# led-drv-noemi.net
KiCad netlist of a schematic drawn in EAGLE
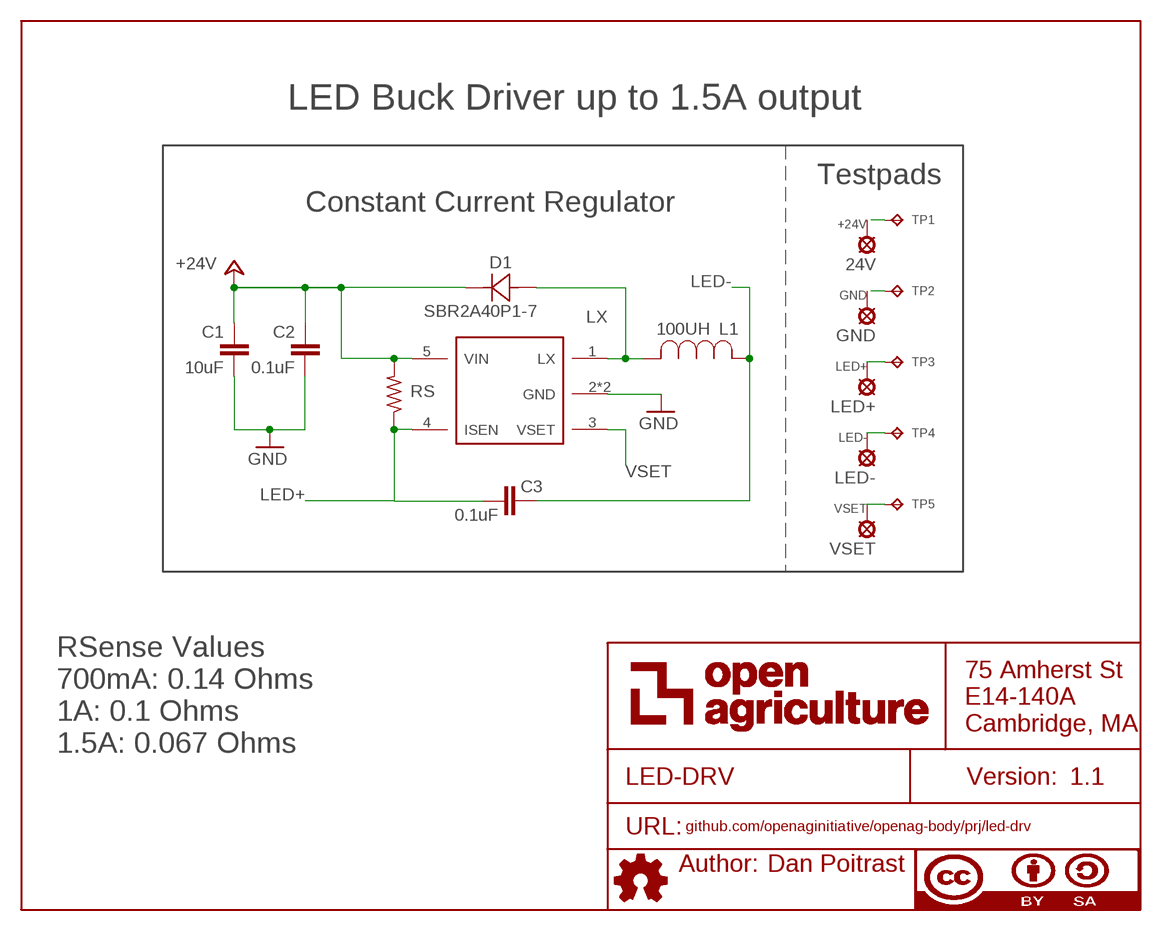
[diagram p0: schematic, sheet 1]

(export (version "E")
  (design (tool "Eeschema 10.0.6"))
  (components
    (comp (ref "24V")
      (value "SE14")
      (footprint "eagle-import:SE14")
      (libsource (lib "eagle-import") (part "SE14"))
    )
    (comp (ref "C1")
      (value "10uF")
      (footprint "eagle-import:C0805")
      (fields (field (name "MANUFACTURER") "Taiyo Yuden") (field (name "MPN") "GMK212BBJ106KG-T"))
      (libsource (lib "eagle-import") (part "10UF-GMK212BBJ106KG-T"))
    )
    (comp (ref "C2")
      (value "0.1uF")
      (footprint "eagle-import:C0603")
      (fields (field (name "MANUFACTURER") "Kemet") (field (name "MPN") "C0603C104K5RACTU"))
      (libsource (lib "eagle-import") (part "0.1UF-C0603C104K5RACTU"))
    )
    (comp (ref "C3")
      (value "0.1uF")
      (footprint "eagle-import:C0603")
      (fields (field (name "MANUFACTURER") "Kemet") (field (name "MPN") "C0603C104K5RACTU"))
      (libsource (lib "eagle-import") (part "0.1UF-C0603C104K5RACTU"))
    )
    (comp (ref "D1")
      (value "SBR2A40P1-7")
      (footprint "eagle-import:POWERDI123")
      (fields (field (name "MANUFACTURER") "Diodes Incorporated"))
      (libsource (lib "eagle-import") (part "SBR2A40P1-7"))
    )
    (comp (ref "GND")
      (value "SE14")
      (footprint "eagle-import:SE14")
      (libsource (lib "eagle-import") (part "SE14"))
    )
    (comp (ref "L1")
      (value "100UH")
      (footprint "eagle-import:IND_BOURNS_SDR1307")
      (libsource (lib "eagle-import") (part "100UH_BOURNES"))
    )
    (comp (ref "LED+")
      (value "SE14")
      (footprint "eagle-import:SE14")
      (libsource (lib "eagle-import") (part "SE14"))
    )
    (comp (ref "LED-")
      (value "SE14")
      (footprint "eagle-import:SE14")
      (libsource (lib "eagle-import") (part "SE14"))
    )
    (comp (ref "RS")
      (value ".06 ohms")
      (footprint "eagle-import:R0805")
      (libsource (lib "eagle-import") (part "6.3OHM-RC0805FR-076R34L"))
    )
    (comp (ref "TP1")
      (value "TPTP06R")
      (footprint "eagle-import:TP06R")
      (libsource (lib "eagle-import") (part "TPTP06R"))
    )
    (comp (ref "TP2")
      (value "TPTP06R")
      (footprint "eagle-import:TP06R")
      (libsource (lib "eagle-import") (part "TPTP06R"))
    )
    (comp (ref "TP3")
      (value "TPTP06R")
      (footprint "eagle-import:TP06R")
      (libsource (lib "eagle-import") (part "TPTP06R"))
    )
    (comp (ref "TP4")
      (value "TPTP06R")
      (footprint "eagle-import:TP06R")
      (libsource (lib "eagle-import") (part "TPTP06R"))
    )
    (comp (ref "TP5")
      (value "TPTP06R")
      (footprint "eagle-import:TP06R")
      (libsource (lib "eagle-import") (part "TPTP06R"))
    )
    (comp (ref "U$6")
      (value "AUTHOR")
      (footprint "eagle-import:AUTHOR")
      (fields (field (name "AUTHOR") "Dan Poitrast"))
      (libsource (lib "eagle-import") (part "AUTHOR"))
    )
    (comp (ref "U$7")
      (value "TITLE")
      (footprint "eagle-import:TITLE")
      (fields
        (field (name "TITLE") "LED-DRV")
        (field (name "URL") "github.com/openaginitiative/openag-body/prj/led-drv")
        (field (name "VER") "1.1")
      )
      (libsource (lib "eagle-import") (part "TITLE"))
    )
    (comp (ref "U$9")
      (value "AL8861")
      (footprint "eagle-import:AL8861")
      (libsource (lib "eagle-import") (part "AL8861"))
    )
    (comp (ref "VSET")
      (value "SE14")
      (footprint "eagle-import:SE14")
      (libsource (lib "eagle-import") (part "SE14"))
    )
  )
  (nets
    (net (code "1") (name "+24V") (class "Default")
      (node (ref "24V") (pin "MP") (pinfunction "MP_MP") (pintype "passive"))
      (node (ref "C1") (pin "1") (pinfunction "1_1") (pintype "passive"))
      (node (ref "C2") (pin "1") (pinfunction "1_1") (pintype "passive"))
      (node (ref "D1") (pin "-") (pinfunction "-_-") (pintype "passive"))
      (node (ref "RS") (pin "2") (pinfunction "2_2") (pintype "passive"))
      (node (ref "TP1") (pin "TP") (pinfunction "TP_TP") (pintype "input"))
      (node (ref "U$9") (pin "5") (pinfunction "VIN_5") (pintype "bidirectional"))
    )
    (net (code "2") (name "/LX") (class "Default")
      (node (ref "D1") (pin "+") (pinfunction "+_+") (pintype "passive"))
      (node (ref "L1") (pin "1") (pinfunction "1_1") (pintype "passive"))
      (node (ref "U$9") (pin "1") (pinfunction "LX_1") (pintype "bidirectional"))
    )
    (net (code "3") (name "GND") (class "Default")
      (node (ref "C1") (pin "2") (pinfunction "2_2") (pintype "passive"))
      (node (ref "C2") (pin "2") (pinfunction "2_2") (pintype "passive"))
      (node (ref "GND") (pin "MP") (pinfunction "MP_MP") (pintype "passive"))
      (node (ref "TP2") (pin "TP") (pinfunction "TP_TP") (pintype "input"))
      (node (ref "U$9") (pin "2") (pinfunction "GND_2") (pintype "bidirectional"))
      (node (ref "U$9") (pin "44") (pinfunction "GND_44") (pintype "bidirectional"))
    )
    (net (code "4") (name "LED+") (class "Default")
      (node (ref "C3") (pin "2") (pinfunction "2_2") (pintype "passive"))
      (node (ref "LED+") (pin "MP") (pinfunction "MP_MP") (pintype "passive"))
      (node (ref "RS") (pin "1") (pinfunction "1_1") (pintype "passive"))
      (node (ref "TP3") (pin "TP") (pinfunction "TP_TP") (pintype "input"))
      (node (ref "U$9") (pin "4") (pinfunction "ISEN_4") (pintype "bidirectional"))
    )
    (net (code "5") (name "LED-") (class "Default")
      (node (ref "C3") (pin "1") (pinfunction "1_1") (pintype "passive"))
      (node (ref "L1") (pin "2") (pinfunction "2_2") (pintype "passive"))
      (node (ref "LED-") (pin "MP") (pinfunction "MP_MP") (pintype "passive"))
      (node (ref "TP4") (pin "TP") (pinfunction "TP_TP") (pintype "input"))
    )
    (net (code "6") (name "VSET") (class "Default")
      (node (ref "TP5") (pin "TP") (pinfunction "TP_TP") (pintype "input"))
      (node (ref "U$9") (pin "3") (pinfunction "VSET_3") (pintype "bidirectional"))
      (node (ref "VSET") (pin "MP") (pinfunction "MP_MP") (pintype "passive"))
    )
  )
)
